# I2Cpad.net
KiCad netlist of a schematic drawn in Altium Designer
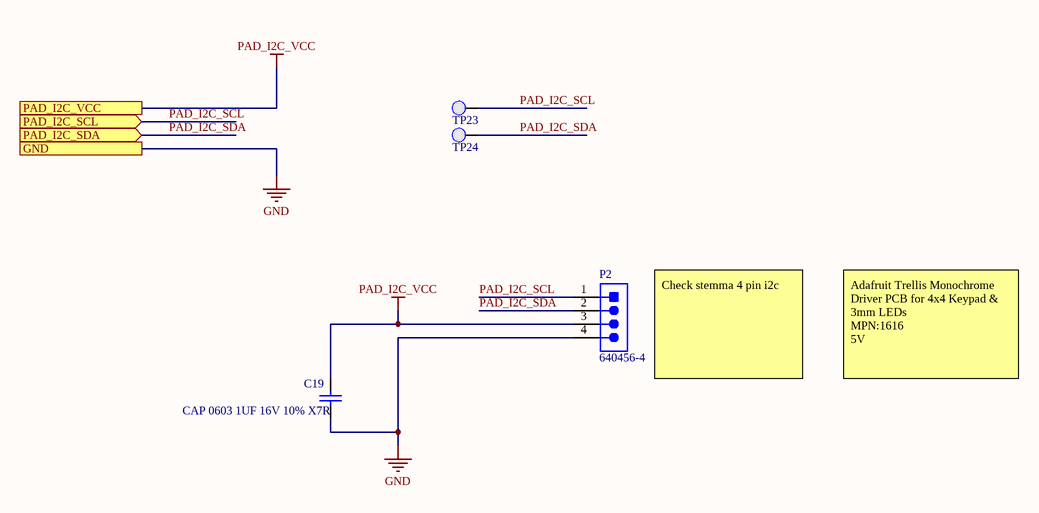
[diagram p0: I2Cpad.SchDoc]

(export (version "E")
  (design (tool "Eeschema 10.0.6"))
  (components
    (comp (ref "C19")
      (value "CAP 0603 1UF 16V 10% X7R")
      (footprint "0603_CAP")
      (description "Capacitor Surface Mount 0603 Footprint 1UF 16V 10% Tolerance Ceramic X7R")
      (fields (field (name "MANUFACTURER") "Various"))
      (libsource (lib "University of Pennsylvania (ESE Labs)") (part "cap"))
    )
    (comp (ref "P2")
      (value "640456-4")
      (footprint "TECO-640456-4")
      (description "Male Header, Pitch 2.54 mm, 1 x 4 Position, Height 10.03 mm, Tail Length 3.56 mm, RoHS, Bulk")
      (fields (field (name "MANUFACTURER") "TE Connectivity"))
      (libsource (lib "Altium Content Vault") (part "CN-1P-M-R4"))
    )
    (comp (ref "TP23")
      (value "Test Point 0.1\"")
      (footprint "Test Point 0.1\"-Footprint-1")
      (libsource (lib "University of Pennsylvania (ESE Labs)") (part "Test Point 0.1{dblquote}-Symbol-1"))
    )
    (comp (ref "TP24")
      (value "Test Point 0.1\"")
      (footprint "Test Point 0.1\"-Footprint-1")
      (libsource (lib "University of Pennsylvania (ESE Labs)") (part "Test Point 0.1{dblquote}-Symbol-1"))
    )
  )
  (nets
    (net (code "1") (name "/PAD_I2C_SCL") (class "Default")
      (node (ref "P2") (pin "1") (pinfunction "1_1") (pintype "passive"))
      (node (ref "TP23") (pin "1") (pinfunction "PAD_1") (pintype "passive"))
    )
    (net (code "2") (name "/PAD_I2C_SDA") (class "Default")
      (node (ref "P2") (pin "2") (pinfunction "2_2") (pintype "passive"))
      (node (ref "TP24") (pin "1") (pinfunction "PAD_1") (pintype "passive"))
    )
    (net (code "3") (name "GND") (class "Default")
      (node (ref "C19") (pin "1") (pinfunction "1_1") (pintype "passive"))
      (node (ref "P2") (pin "4") (pinfunction "4_4") (pintype "passive"))
    )
    (net (code "4") (name "PAD_I2C_VCC") (class "Default")
      (node (ref "C19") (pin "2") (pinfunction "2_2") (pintype "passive"))
      (node (ref "P2") (pin "3") (pinfunction "3_3") (pintype "passive"))
    )
  )
)
